# motorboard_simp_power.net
KiCad netlist of a schematic drawn in Altium Designer
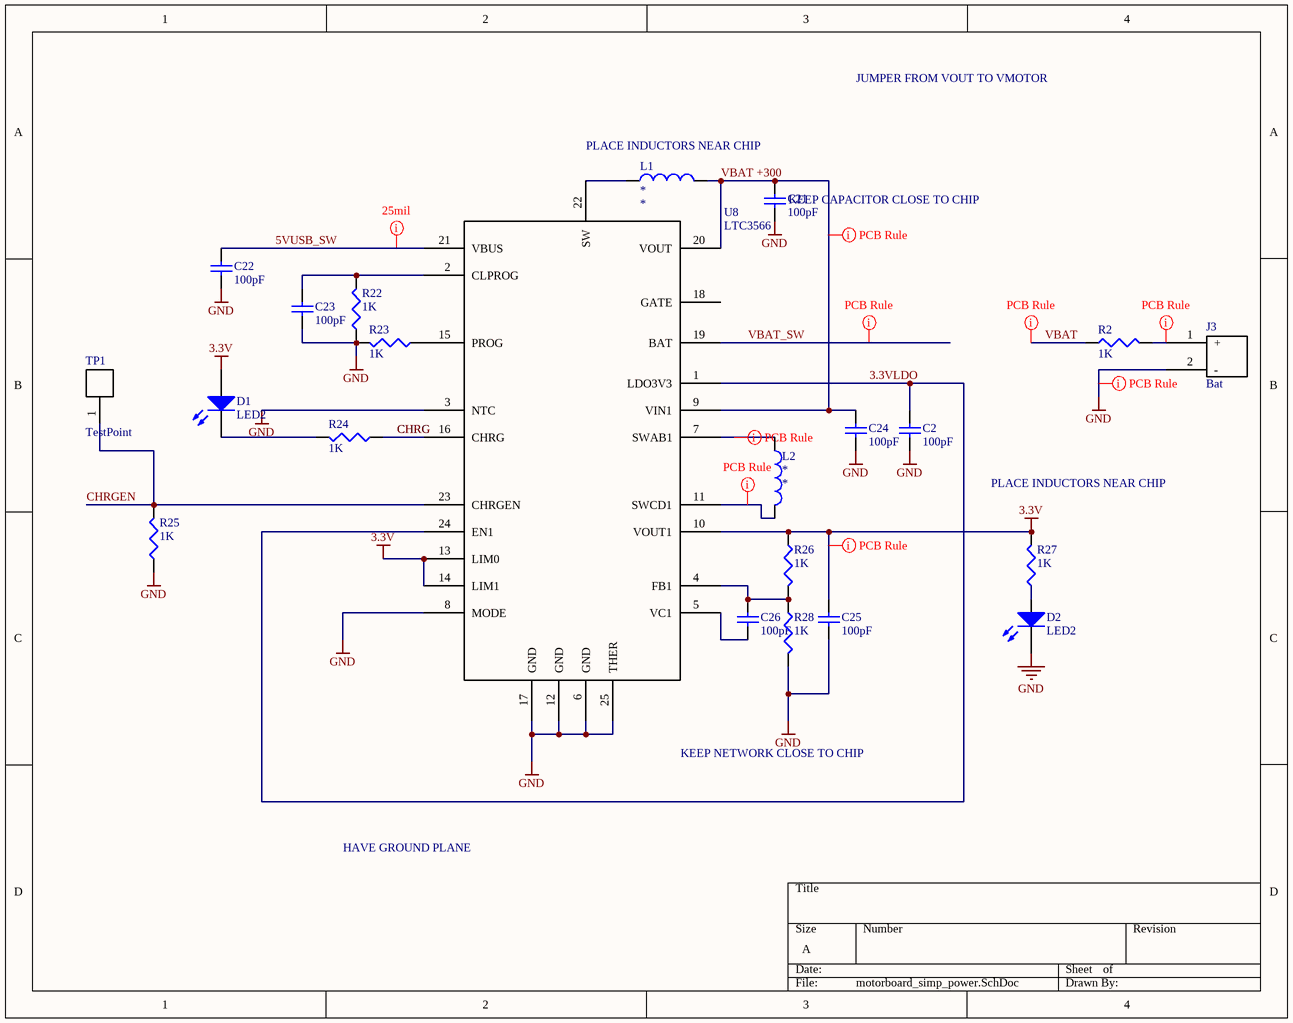
[diagram p0: motorboard_simp_power.SchDoc]

(export (version "E")
  (design (tool "Eeschema 10.0.6"))
  (components
    (comp (ref "C2")
      (value "100pF")
      (footprint "RAD-0.3")
      (description "Capacitor")
      (fields (field (name "Comment") "Cap") (field (name "PUBLISHER") "Altium Limited"))
      (libsource (lib "Miscellaneous Devices") (part "Cap"))
    )
    (comp (ref "C21")
      (value "100pF")
      (footprint "RAD-0.3")
      (description "Capacitor")
      (fields (field (name "Comment") "Cap") (field (name "PUBLISHER") "Altium Limited"))
      (libsource (lib "Miscellaneous Devices") (part "Cap"))
    )
    (comp (ref "C22")
      (value "100pF")
      (footprint "RAD-0.3")
      (description "Capacitor")
      (fields (field (name "Comment") "Cap") (field (name "PUBLISHER") "Altium Limited"))
      (libsource (lib "Miscellaneous Devices") (part "Cap"))
    )
    (comp (ref "C23")
      (value "100pF")
      (footprint "RAD-0.3")
      (description "Capacitor")
      (fields (field (name "Comment") "Cap") (field (name "PUBLISHER") "Altium Limited"))
      (libsource (lib "Miscellaneous Devices") (part "Cap"))
    )
    (comp (ref "C24")
      (value "100pF")
      (footprint "RAD-0.3")
      (description "Capacitor")
      (fields (field (name "Comment") "Cap") (field (name "PUBLISHER") "Altium Limited"))
      (libsource (lib "Miscellaneous Devices") (part "Cap"))
    )
    (comp (ref "C25")
      (value "100pF")
      (footprint "RAD-0.3")
      (description "Capacitor")
      (fields (field (name "Comment") "Cap") (field (name "PUBLISHER") "Altium Limited"))
      (libsource (lib "Miscellaneous Devices") (part "Cap"))
    )
    (comp (ref "C26")
      (value "100pF")
      (footprint "RAD-0.3")
      (description "Capacitor")
      (fields (field (name "Comment") "Cap") (field (name "PUBLISHER") "Altium Limited"))
      (libsource (lib "Miscellaneous Devices") (part "Cap"))
    )
    (comp (ref "D1")
      (value "LED2")
      (footprint "DSO-F2/D6.1")
      (description "Typical RED, GREEN, YELLOW, AMBER GaAs LED")
      (fields (field (name "PUBLISHER") "Altium Limited"))
      (libsource (lib "Miscellaneous Devices") (part "LED2"))
    )
    (comp (ref "D2")
      (value "LED2")
      (footprint "DSO-F2/D6.1")
      (description "Typical RED, GREEN, YELLOW, AMBER GaAs LED")
      (fields (field (name "PUBLISHER") "Altium Limited"))
      (libsource (lib "Miscellaneous Devices") (part "LED2"))
    )
    (comp (ref "J3")
      (value "Bat")
      (footprint "BatteryConnJST")
      (libsource (lib "mrone") (part "BatteryConnJST"))
    )
    (comp (ref "L1")
      (value "*")
      (footprint "Inductor-Power")
      (fields (field (name "ALTIUM_VALUE") "*"))
      (libsource (lib "mrone") (part "Inductor"))
    )
    (comp (ref "L2")
      (value "*")
      (footprint "Inductor-Power")
      (fields (field (name "ALTIUM_VALUE") "*"))
      (libsource (lib "mrone") (part "Inductor"))
    )
    (comp (ref "R2")
      (value "1K")
      (footprint "RESC1608L")
      (description "Resistor")
      (fields (field (name "Comment") "Res3") (field (name "PUBLISHER") "Altium Limited"))
      (libsource (lib "Miscellaneous Devices") (part "Res3"))
    )
    (comp (ref "R22")
      (value "1K")
      (footprint "RESC1608L")
      (description "Resistor")
      (fields (field (name "Comment") "Res3") (field (name "PUBLISHER") "Altium Limited"))
      (libsource (lib "Miscellaneous Devices") (part "Res3"))
    )
    (comp (ref "R23")
      (value "1K")
      (footprint "RESC1608L")
      (description "Resistor")
      (fields (field (name "Comment") "Res3") (field (name "PUBLISHER") "Altium Limited"))
      (libsource (lib "Miscellaneous Devices") (part "Res3"))
    )
    (comp (ref "R24")
      (value "1K")
      (footprint "RESC1608L")
      (description "Resistor")
      (fields (field (name "Comment") "Res3") (field (name "PUBLISHER") "Altium Limited"))
      (libsource (lib "Miscellaneous Devices") (part "Res3"))
    )
    (comp (ref "R25")
      (value "1K")
      (footprint "RESC1608L")
      (description "Resistor")
      (fields (field (name "Comment") "Res3") (field (name "PUBLISHER") "Altium Limited"))
      (libsource (lib "Miscellaneous Devices") (part "Res3"))
    )
    (comp (ref "R26")
      (value "1K")
      (footprint "RESC1608L")
      (description "Resistor")
      (fields (field (name "Comment") "Res3") (field (name "PUBLISHER") "Altium Limited"))
      (libsource (lib "Miscellaneous Devices") (part "Res3"))
    )
    (comp (ref "R27")
      (value "1K")
      (footprint "RESC1608L")
      (description "Resistor")
      (fields (field (name "Comment") "Res3") (field (name "PUBLISHER") "Altium Limited"))
      (libsource (lib "Miscellaneous Devices") (part "Res3"))
    )
    (comp (ref "R28")
      (value "1K")
      (footprint "RESC1608L")
      (description "Resistor")
      (fields (field (name "Comment") "Res3") (field (name "PUBLISHER") "Altium Limited"))
      (libsource (lib "Miscellaneous Devices") (part "Res3"))
    )
    (comp (ref "TP1")
      (value "TestPoint")
      (footprint "TestPoint")
      (libsource (lib "mrone") (part "TestPoint"))
    )
    (comp (ref "U8")
      (value "LTC3566")
      (footprint "QFN-24")
      (libsource (lib "Schematic Components") (part "LTC3566"))
    )
  )
  (nets
    (net (code "1") (name "/3.3VLDO") (class "Default")
      (node (ref "C2") (pin "1") (pinfunction "1_1") (pintype "passive"))
      (node (ref "U8") (pin "1") (pinfunction "LDO3V3_1") (pintype "passive"))
      (node (ref "U8") (pin "24") (pinfunction "EN1_24") (pintype "passive"))
    )
    (net (code "2") (name "/5VUSB_SW") (class "Default")
      (node (ref "C22") (pin "2") (pinfunction "2_2") (pintype "passive"))
      (node (ref "U8") (pin "21") (pinfunction "VBUS_21") (pintype "passive"))
    )
    (net (code "3") (name "/CHRG") (class "Default")
      (node (ref "R24") (pin "1") (pinfunction "1_1") (pintype "passive"))
      (node (ref "U8") (pin "16") (pinfunction "CHRG_16") (pintype "passive"))
    )
    (net (code "4") (name "/CHRGEN") (class "Default")
      (node (ref "R25") (pin "2") (pinfunction "2_2") (pintype "passive"))
      (node (ref "TP1") (pin "1") (pintype "passive"))
      (node (ref "U8") (pin "23") (pinfunction "CHRGEN_23") (pintype "passive"))
    )
    (net (code "5") (name "/VBAT") (class "Default")
      (node (ref "R2") (pin "1") (pinfunction "1_1") (pintype "passive"))
    )
    (net (code "6") (name "/VBAT +300") (class "Default")
      (node (ref "C21") (pin "2") (pinfunction "2_2") (pintype "passive"))
      (node (ref "C24") (pin "1") (pinfunction "1_1") (pintype "passive"))
      (node (ref "L1") (pin "2") (pinfunction "2_2") (pintype "passive"))
      (node (ref "U8") (pin "20") (pinfunction "VOUT_20") (pintype "passive"))
      (node (ref "U8") (pin "9") (pinfunction "VIN1_9") (pintype "passive"))
    )
    (net (code "7") (name "/VBAT_SW") (class "Default")
      (node (ref "U8") (pin "19") (pinfunction "BAT_19") (pintype "passive"))
    )
    (net (code "8") (name "3.3V") (class "Default")
      (node (ref "C25") (pin "2") (pinfunction "2_2") (pintype "passive"))
      (node (ref "D1") (pin "1") (pinfunction "A_1") (pintype "passive"))
      (node (ref "R26") (pin "1") (pinfunction "1_1") (pintype "passive"))
      (node (ref "R27") (pin "2") (pinfunction "2_2") (pintype "passive"))
      (node (ref "U8") (pin "10") (pinfunction "VOUT1_10") (pintype "passive"))
      (node (ref "U8") (pin "13") (pinfunction "LIM0_13") (pintype "passive"))
      (node (ref "U8") (pin "14") (pinfunction "LIM1_14") (pintype "passive"))
    )
    (net (code "9") (name "GND") (class "Default")
      (node (ref "C2") (pin "2") (pinfunction "2_2") (pintype "passive"))
      (node (ref "C21") (pin "1") (pinfunction "1_1") (pintype "passive"))
      (node (ref "C22") (pin "1") (pinfunction "1_1") (pintype "passive"))
      (node (ref "C23") (pin "1") (pinfunction "1_1") (pintype "passive"))
      (node (ref "C24") (pin "2") (pinfunction "2_2") (pintype "passive"))
      (node (ref "C25") (pin "1") (pinfunction "1_1") (pintype "passive"))
      (node (ref "D2") (pin "2") (pinfunction "K_2") (pintype "passive"))
      (node (ref "J3") (pin "2") (pinfunction "-_2") (pintype "passive"))
      (node (ref "R22") (pin "1") (pinfunction "1_1") (pintype "passive"))
      (node (ref "R23") (pin "2") (pinfunction "2_2") (pintype "passive"))
      (node (ref "R25") (pin "1") (pinfunction "1_1") (pintype "passive"))
      (node (ref "R28") (pin "2") (pinfunction "2_2") (pintype "passive"))
      (node (ref "U8") (pin "12") (pinfunction "GND_12") (pintype "passive"))
      (node (ref "U8") (pin "17") (pinfunction "GND_17") (pintype "passive"))
      (node (ref "U8") (pin "25") (pinfunction "THER_25") (pintype "passive"))
      (node (ref "U8") (pin "3") (pinfunction "NTC_3") (pintype "passive"))
      (node (ref "U8") (pin "6") (pinfunction "GND_6") (pintype "passive"))
      (node (ref "U8") (pin "8") (pinfunction "MODE_8") (pintype "passive"))
    )
    (net (code "10") (name "Net-(D1-K)") (class "Default")
      (node (ref "D1") (pin "2") (pinfunction "K_2") (pintype "passive"))
      (node (ref "R24") (pin "2") (pinfunction "2_2") (pintype "passive"))
    )
    (net (code "11") (name "Net-(D2-A)") (class "Default")
      (node (ref "D2") (pin "1") (pinfunction "A_1") (pintype "passive"))
      (node (ref "R27") (pin "1") (pinfunction "1_1") (pintype "passive"))
    )
    (net (code "12") (name "Net-(J3-+)") (class "Default")
      (node (ref "J3") (pin "1") (pinfunction "+_1") (pintype "passive"))
      (node (ref "R2") (pin "2") (pinfunction "2_2") (pintype "passive"))
    )
    (net (code "13") (name "Net-(U8-CLPROG)") (class "Default")
      (node (ref "C23") (pin "2") (pinfunction "2_2") (pintype "passive"))
      (node (ref "R22") (pin "2") (pinfunction "2_2") (pintype "passive"))
      (node (ref "U8") (pin "2") (pinfunction "CLPROG_2") (pintype "passive"))
    )
    (net (code "14") (name "Net-(U8-FB1)") (class "Default")
      (node (ref "C26") (pin "1") (pinfunction "1_1") (pintype "passive"))
      (node (ref "R26") (pin "2") (pinfunction "2_2") (pintype "passive"))
      (node (ref "R28") (pin "1") (pinfunction "1_1") (pintype "passive"))
      (node (ref "U8") (pin "4") (pinfunction "FB1_4") (pintype "passive"))
    )
    (net (code "15") (name "Net-(U8-PROG)") (class "Default")
      (node (ref "R23") (pin "1") (pinfunction "1_1") (pintype "passive"))
      (node (ref "U8") (pin "15") (pinfunction "PROG_15") (pintype "passive"))
    )
    (net (code "16") (name "Net-(U8-SW)") (class "Default")
      (node (ref "L1") (pin "1") (pinfunction "1_1") (pintype "passive"))
      (node (ref "U8") (pin "22") (pinfunction "SW_22") (pintype "passive"))
    )
    (net (code "17") (name "Net-(U8-SWAB1)") (class "Default")
      (node (ref "L2") (pin "1") (pinfunction "1_1") (pintype "passive"))
      (node (ref "U8") (pin "7") (pinfunction "SWAB1_7") (pintype "passive"))
    )
    (net (code "18") (name "Net-(U8-SWCD1)") (class "Default")
      (node (ref "L2") (pin "2") (pinfunction "2_2") (pintype "passive"))
      (node (ref "U8") (pin "11") (pinfunction "SWCD1_11") (pintype "passive"))
    )
    (net (code "19") (name "Net-(U8-VC1)") (class "Default")
      (node (ref "C26") (pin "2") (pinfunction "2_2") (pintype "passive"))
      (node (ref "U8") (pin "5") (pinfunction "VC1_5") (pintype "passive"))
    )
    (net (code "20") (name "unconnected-(U8-GATE-Pad18)") (class "Default")
      (node (ref "U8") (pin "18") (pinfunction "GATE_18") (pintype "passive"))
    )
  )
)
